# MC.net
KiCad netlist of a schematic drawn in Altium Designer
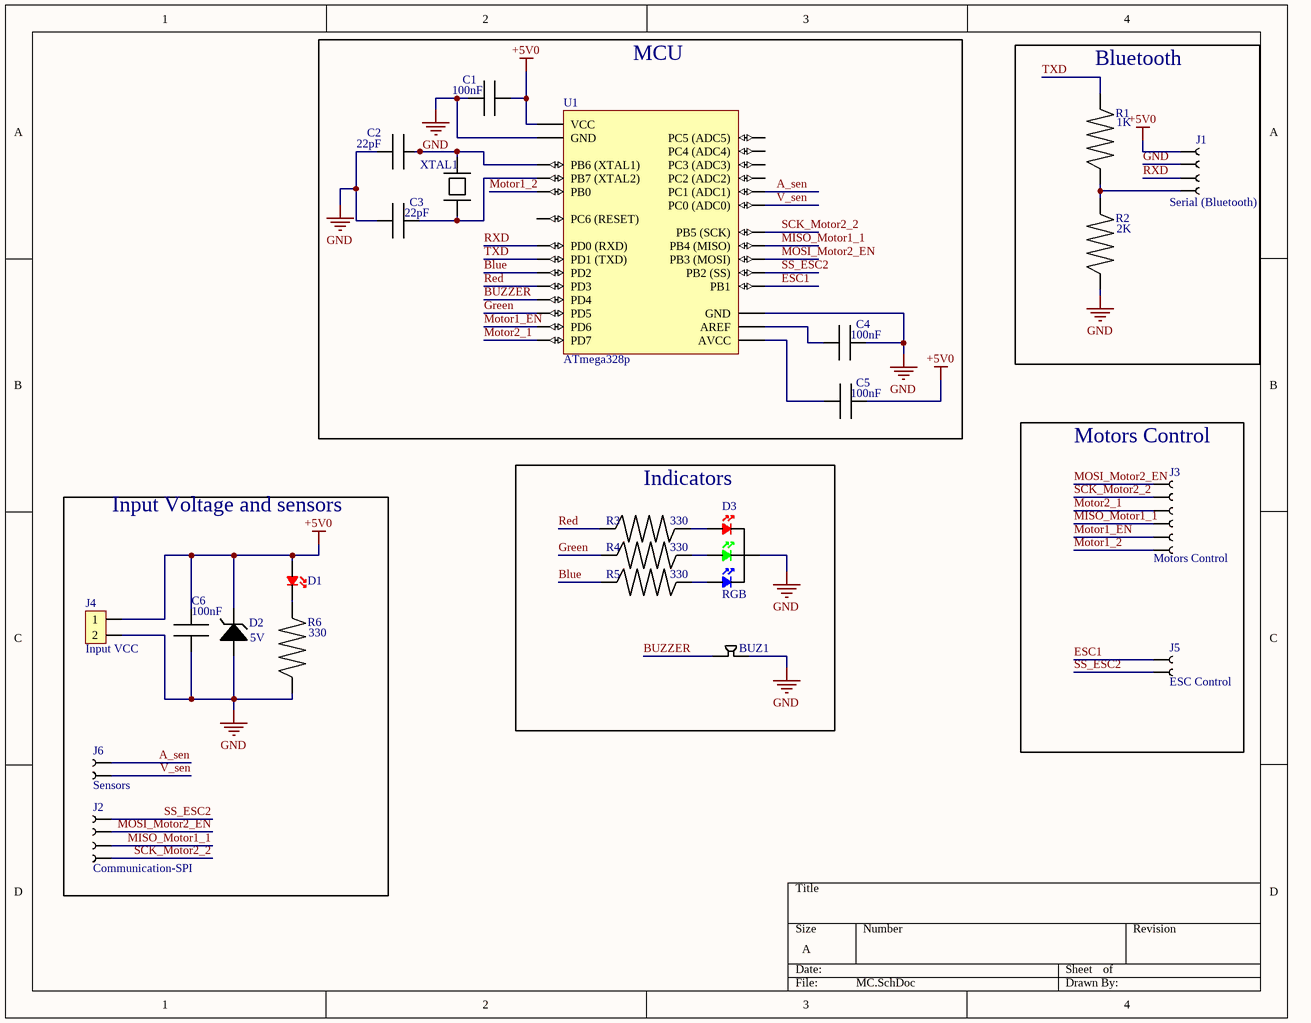
[diagram p0: MC.SchDoc]

(export (version "E")
  (design (tool "Eeschema 10.0.6"))
  (components
    (comp (ref "BUZ1") (value "BUZZER") (footprint "Buzzer") (libsource (lib "Components") (part "BUZZER")))
    (comp (ref "C1")
      (value "100nF")
      (footprint "Ceramic Cap")
      (fields (field (name "Comment") "Ceramic Capacitor"))
      (libsource (lib "Components") (part "Ceramic Capacitor"))
    )
    (comp (ref "C2")
      (value "22pF")
      (footprint "Ceramic Cap")
      (fields (field (name "Comment") "Ceramic Capacitor"))
      (libsource (lib "Components") (part "Ceramic Capacitor"))
    )
    (comp (ref "C3")
      (value "22pF")
      (footprint "Ceramic Cap")
      (fields (field (name "Comment") "Ceramic Capacitor"))
      (libsource (lib "Components") (part "Ceramic Capacitor"))
    )
    (comp (ref "C4")
      (value "100nF")
      (footprint "Ceramic Cap")
      (fields (field (name "Comment") "Ceramic Capacitor"))
      (libsource (lib "Components") (part "Ceramic Capacitor"))
    )
    (comp (ref "C5")
      (value "100nF")
      (footprint "Ceramic Cap")
      (fields (field (name "Comment") "Ceramic Capacitor"))
      (libsource (lib "Components") (part "Ceramic Capacitor"))
    )
    (comp (ref "C6")
      (value "100nF")
      (footprint "Ceramic Cap")
      (fields (field (name "Comment") "Ceramic Capacitor"))
      (libsource (lib "Components") (part "Ceramic Capacitor"))
    )
    (comp (ref "D1") (value "LED") (footprint "LED5MM") (libsource (lib "Components") (part "LED")))
    (comp (ref "D2")
      (value "5V")
      (footprint "Zener10")
      (fields (field (name "Comment") "Zener"))
      (libsource (lib "Components") (part "Zener"))
    )
    (comp (ref "D3") (value "RGB") (footprint "RGB") (libsource (lib "Components") (part "RGB")))
    (comp (ref "J1")
      (value "Serial (Bluetooth)")
      (footprint "Headers-4")
      (libsource (lib "Components") (part "Headers-4"))
    )
    (comp (ref "J2")
      (value "Communication-SPI")
      (footprint "Headers-4")
      (libsource (lib "Components") (part "Headers-4"))
    )
    (comp (ref "J3")
      (value "Motors Control")
      (footprint "Headers 6-pins")
      (libsource (lib "Components") (part "Headers-6"))
    )
    (comp (ref "J4")
      (value "Input VCC")
      (footprint "Terminal Block 2 Plugable")
      (fields (field (name "MF") "Phoenix Contact"))
      (libsource (lib "Components") (part "Terminal Block 2-pins"))
    )
    (comp (ref "J5")
      (value "ESC Control")
      (footprint "Headers 2-Pins")
      (libsource (lib "Components") (part "Header-2"))
    )
    (comp (ref "J6")
      (value "Sensors")
      (footprint "Headers 2-Pins")
      (libsource (lib "Components") (part "Header-2"))
    )
    (comp (ref "R1")
      (value "1K")
      (footprint "resistor")
      (fields (field (name "Comment") "Resistor"))
      (libsource (lib "Components") (part "Resistor"))
    )
    (comp (ref "R2")
      (value "2K")
      (footprint "resistor")
      (fields (field (name "Comment") "Resistor"))
      (libsource (lib "Components") (part "Resistor"))
    )
    (comp (ref "R3")
      (value "330")
      (footprint "resistor")
      (fields (field (name "Comment") "Resistor"))
      (libsource (lib "Components") (part "Resistor"))
    )
    (comp (ref "R4")
      (value "330")
      (footprint "resistor")
      (fields (field (name "Comment") "Resistor"))
      (libsource (lib "Components") (part "Resistor"))
    )
    (comp (ref "R5")
      (value "330")
      (footprint "resistor")
      (fields (field (name "Comment") "Resistor"))
      (libsource (lib "Components") (part "Resistor"))
    )
    (comp (ref "R6")
      (value "330")
      (footprint "resistor")
      (fields (field (name "Comment") "Resistor"))
      (libsource (lib "Components") (part "Resistor"))
    )
    (comp (ref "U1")
      (value "ATmega328p")
      (footprint "ATmega328PU")
      (fields (field (name "MF") "ATmel"))
      (libsource (lib "Components") (part "ATmega328p"))
    )
    (comp (ref "XTAL1")
      (value "Crystal")
      (footprint "Crystal")
      (libsource (lib "Components") (part "Crystal"))
    )
  )
  (nets
    (net (code "1") (name "+5V0") (class "Default")
      (node (ref "C1") (pin "2") (pintype "passive"))
      (node (ref "C5") (pin "2") (pintype "passive"))
      (node (ref "C6") (pin "2") (pintype "passive"))
      (node (ref "D1") (pin "A") (pinfunction "A_A") (pintype "passive"))
      (node (ref "D2") (pin "2") (pinfunction "Cath_2") (pintype "passive"))
      (node (ref "J1") (pin "4") (pintype "passive"))
      (node (ref "J4") (pin "1") (pinfunction "1_1") (pintype "passive"))
      (node (ref "U1") (pin "7") (pinfunction "VCC_7") (pintype "power_in"))
    )
    (net (code "2") (name "/A_sen") (class "Default")
      (node (ref "J6") (pin "1") (pintype "passive"))
      (node (ref "U1") (pin "24") (pinfunction "PC1_(ADC1)_24") (pintype "bidirectional"))
    )
    (net (code "3") (name "/BUZZER") (class "Default")
      (node (ref "BUZ1") (pin "1") (pinfunction "1_1") (pintype "passive"))
      (node (ref "U1") (pin "6") (pinfunction "PD4_6") (pintype "bidirectional"))
    )
    (net (code "4") (name "/Blue") (class "Default")
      (node (ref "R5") (pin "1") (pinfunction "13_1") (pintype "passive"))
      (node (ref "U1") (pin "4") (pinfunction "PD2_4") (pintype "bidirectional"))
    )
    (net (code "5") (name "/ESC1") (class "Default")
      (node (ref "J5") (pin "2") (pintype "passive"))
      (node (ref "U1") (pin "15") (pinfunction "PB1_15") (pintype "bidirectional"))
    )
    (net (code "6") (name "/Green") (class "Default")
      (node (ref "R4") (pin "1") (pinfunction "13_1") (pintype "passive"))
      (node (ref "U1") (pin "11") (pinfunction "PD5_11") (pintype "bidirectional"))
    )
    (net (code "7") (name "/MISO_Motor1_1") (class "Default")
      (node (ref "J2") (pin "3") (pintype "passive"))
      (node (ref "J3") (pin "3") (pintype "passive"))
      (node (ref "U1") (pin "18") (pinfunction "PB4_(MISO)_18") (pintype "bidirectional"))
    )
    (net (code "8") (name "/MOSI_Motor2_EN") (class "Default")
      (node (ref "J2") (pin "2") (pintype "passive"))
      (node (ref "J3") (pin "6") (pintype "passive"))
      (node (ref "U1") (pin "17") (pinfunction "PB3_(MOSI)_17") (pintype "bidirectional"))
    )
    (net (code "9") (name "/Motor1_2") (class "Default")
      (node (ref "J3") (pin "1") (pintype "passive"))
      (node (ref "U1") (pin "14") (pinfunction "PB0_14") (pintype "bidirectional"))
    )
    (net (code "10") (name "/Motor1_EN") (class "Default")
      (node (ref "J3") (pin "2") (pintype "passive"))
      (node (ref "U1") (pin "12") (pinfunction "PD6_12") (pintype "bidirectional"))
    )
    (net (code "11") (name "/Motor2_1") (class "Default")
      (node (ref "J3") (pin "4") (pintype "passive"))
      (node (ref "U1") (pin "13") (pinfunction "PD7_13") (pintype "bidirectional"))
    )
    (net (code "12") (name "/RXD") (class "Default")
      (node (ref "J1") (pin "2") (pintype "passive"))
      (node (ref "U1") (pin "2") (pinfunction "PD0_(RXD)_2") (pintype "bidirectional"))
    )
    (net (code "13") (name "/Red") (class "Default")
      (node (ref "R3") (pin "1") (pinfunction "13_1") (pintype "passive"))
      (node (ref "U1") (pin "5") (pinfunction "PD3_5") (pintype "bidirectional"))
    )
    (net (code "14") (name "/SCK_Motor2_2") (class "Default")
      (node (ref "J2") (pin "4") (pintype "passive"))
      (node (ref "J3") (pin "5") (pintype "passive"))
      (node (ref "U1") (pin "19") (pinfunction "PB5_(SCK)_19") (pintype "bidirectional"))
    )
    (net (code "15") (name "/SS_ESC2") (class "Default")
      (node (ref "J2") (pin "1") (pintype "passive"))
      (node (ref "J5") (pin "1") (pintype "passive"))
      (node (ref "U1") (pin "16") (pinfunction "PB2_(SS)_16") (pintype "bidirectional"))
    )
    (net (code "16") (name "/TXD") (class "Default")
      (node (ref "R1") (pin "2") (pinfunction "14_2") (pintype "passive"))
      (node (ref "U1") (pin "3") (pinfunction "PD1_(TXD)_3") (pintype "bidirectional"))
    )
    (net (code "17") (name "/V_sen") (class "Default")
      (node (ref "J6") (pin "2") (pintype "passive"))
      (node (ref "U1") (pin "23") (pinfunction "PC0_(ADC0)_23") (pintype "bidirectional"))
    )
    (net (code "18") (name "GND") (class "Default")
      (node (ref "BUZ1") (pin "2") (pinfunction "2_2") (pintype "passive"))
      (node (ref "C1") (pin "1") (pintype "passive"))
      (node (ref "C2") (pin "1") (pintype "passive"))
      (node (ref "C3") (pin "1") (pintype "passive"))
      (node (ref "C4") (pin "2") (pintype "passive"))
      (node (ref "C6") (pin "1") (pintype "passive"))
      (node (ref "D2") (pin "1") (pinfunction "anode_1") (pintype "passive"))
      (node (ref "D3") (pin "C") (pinfunction "C_C") (pintype "passive"))
      (node (ref "J1") (pin "3") (pintype "passive"))
      (node (ref "J4") (pin "2") (pinfunction "2_2") (pintype "passive"))
      (node (ref "R2") (pin "1") (pinfunction "13_1") (pintype "passive"))
      (node (ref "R6") (pin "1") (pinfunction "13_1") (pintype "passive"))
      (node (ref "U1") (pin "22") (pinfunction "GND_22") (pintype "power_in"))
      (node (ref "U1") (pin "8") (pinfunction "GND_8") (pintype "power_in"))
    )
    (net (code "19") (name "Net-(R1-13)") (class "Default")
      (node (ref "J1") (pin "1") (pintype "passive"))
      (node (ref "R1") (pin "1") (pinfunction "13_1") (pintype "passive"))
      (node (ref "R2") (pin "2") (pinfunction "14_2") (pintype "passive"))
    )
    (net (code "20") (name "Net-(R3-14)") (class "Default")
      (node (ref "D3") (pin "R") (pinfunction "R_R") (pintype "passive"))
      (node (ref "R3") (pin "2") (pinfunction "14_2") (pintype "passive"))
    )
    (net (code "21") (name "Net-(R4-14)") (class "Default")
      (node (ref "D3") (pin "G") (pinfunction "G_G") (pintype "passive"))
      (node (ref "R4") (pin "2") (pinfunction "14_2") (pintype "passive"))
    )
    (net (code "22") (name "Net-(R5-14)") (class "Default")
      (node (ref "D3") (pin "B") (pinfunction "B_B") (pintype "passive"))
      (node (ref "R5") (pin "2") (pinfunction "14_2") (pintype "passive"))
    )
    (net (code "23") (name "Net-(R6-14)") (class "Default")
      (node (ref "D1") (pin "K") (pinfunction "K_K") (pintype "passive"))
      (node (ref "R6") (pin "2") (pinfunction "14_2") (pintype "passive"))
    )
    (net (code "24") (name "Net-(U1-AREF)") (class "Default")
      (node (ref "C4") (pin "1") (pintype "passive"))
      (node (ref "U1") (pin "21") (pinfunction "AREF_21") (pintype "power_in"))
    )
    (net (code "25") (name "Net-(U1-AVCC)") (class "Default")
      (node (ref "C5") (pin "1") (pintype "passive"))
      (node (ref "U1") (pin "20") (pinfunction "AVCC_20") (pintype "power_in"))
    )
    (net (code "26") (name "Net-(U1-PB6_(XTAL1))") (class "Default")
      (node (ref "C2") (pin "2") (pintype "passive"))
      (node (ref "U1") (pin "9") (pinfunction "PB6_(XTAL1)_9") (pintype "bidirectional"))
      (node (ref "XTAL1") (pin "2") (pinfunction "2_2") (pintype "passive"))
    )
    (net (code "27") (name "Net-(U1-PB7_(XTAL2))") (class "Default")
      (node (ref "C3") (pin "2") (pintype "passive"))
      (node (ref "U1") (pin "10") (pinfunction "PB7_(XTAL2)_10") (pintype "bidirectional"))
      (node (ref "XTAL1") (pin "1") (pinfunction "1_1") (pintype "passive"))
    )
    (net (code "28") (name "unconnected-(U1-PC2_(ADC2)-Pad25)") (class "Default")
      (node (ref "U1") (pin "25") (pinfunction "PC2_(ADC2)_25") (pintype "bidirectional"))
    )
    (net (code "29") (name "unconnected-(U1-PC3_(ADC3)-Pad26)") (class "Default")
      (node (ref "U1") (pin "26") (pinfunction "PC3_(ADC3)_26") (pintype "bidirectional"))
    )
    (net (code "30") (name "unconnected-(U1-PC4_(ADC4)-Pad27)") (class "Default")
      (node (ref "U1") (pin "27") (pinfunction "PC4_(ADC4)_27") (pintype "bidirectional"))
    )
    (net (code "31") (name "unconnected-(U1-PC5_(ADC5)-Pad28)") (class "Default")
      (node (ref "U1") (pin "28") (pinfunction "PC5_(ADC5)_28") (pintype "bidirectional"))
    )
    (net (code "32") (name "unconnected-(U1-PC6_(RESET)-Pad1)") (class "Default")
      (node (ref "U1") (pin "1") (pinfunction "PC6_(RESET)_1") (pintype "bidirectional"))
    )
  )
)
